# SparkFun_Qwiic_Motor_Driver.net
KiCad netlist of a schematic drawn in EAGLE
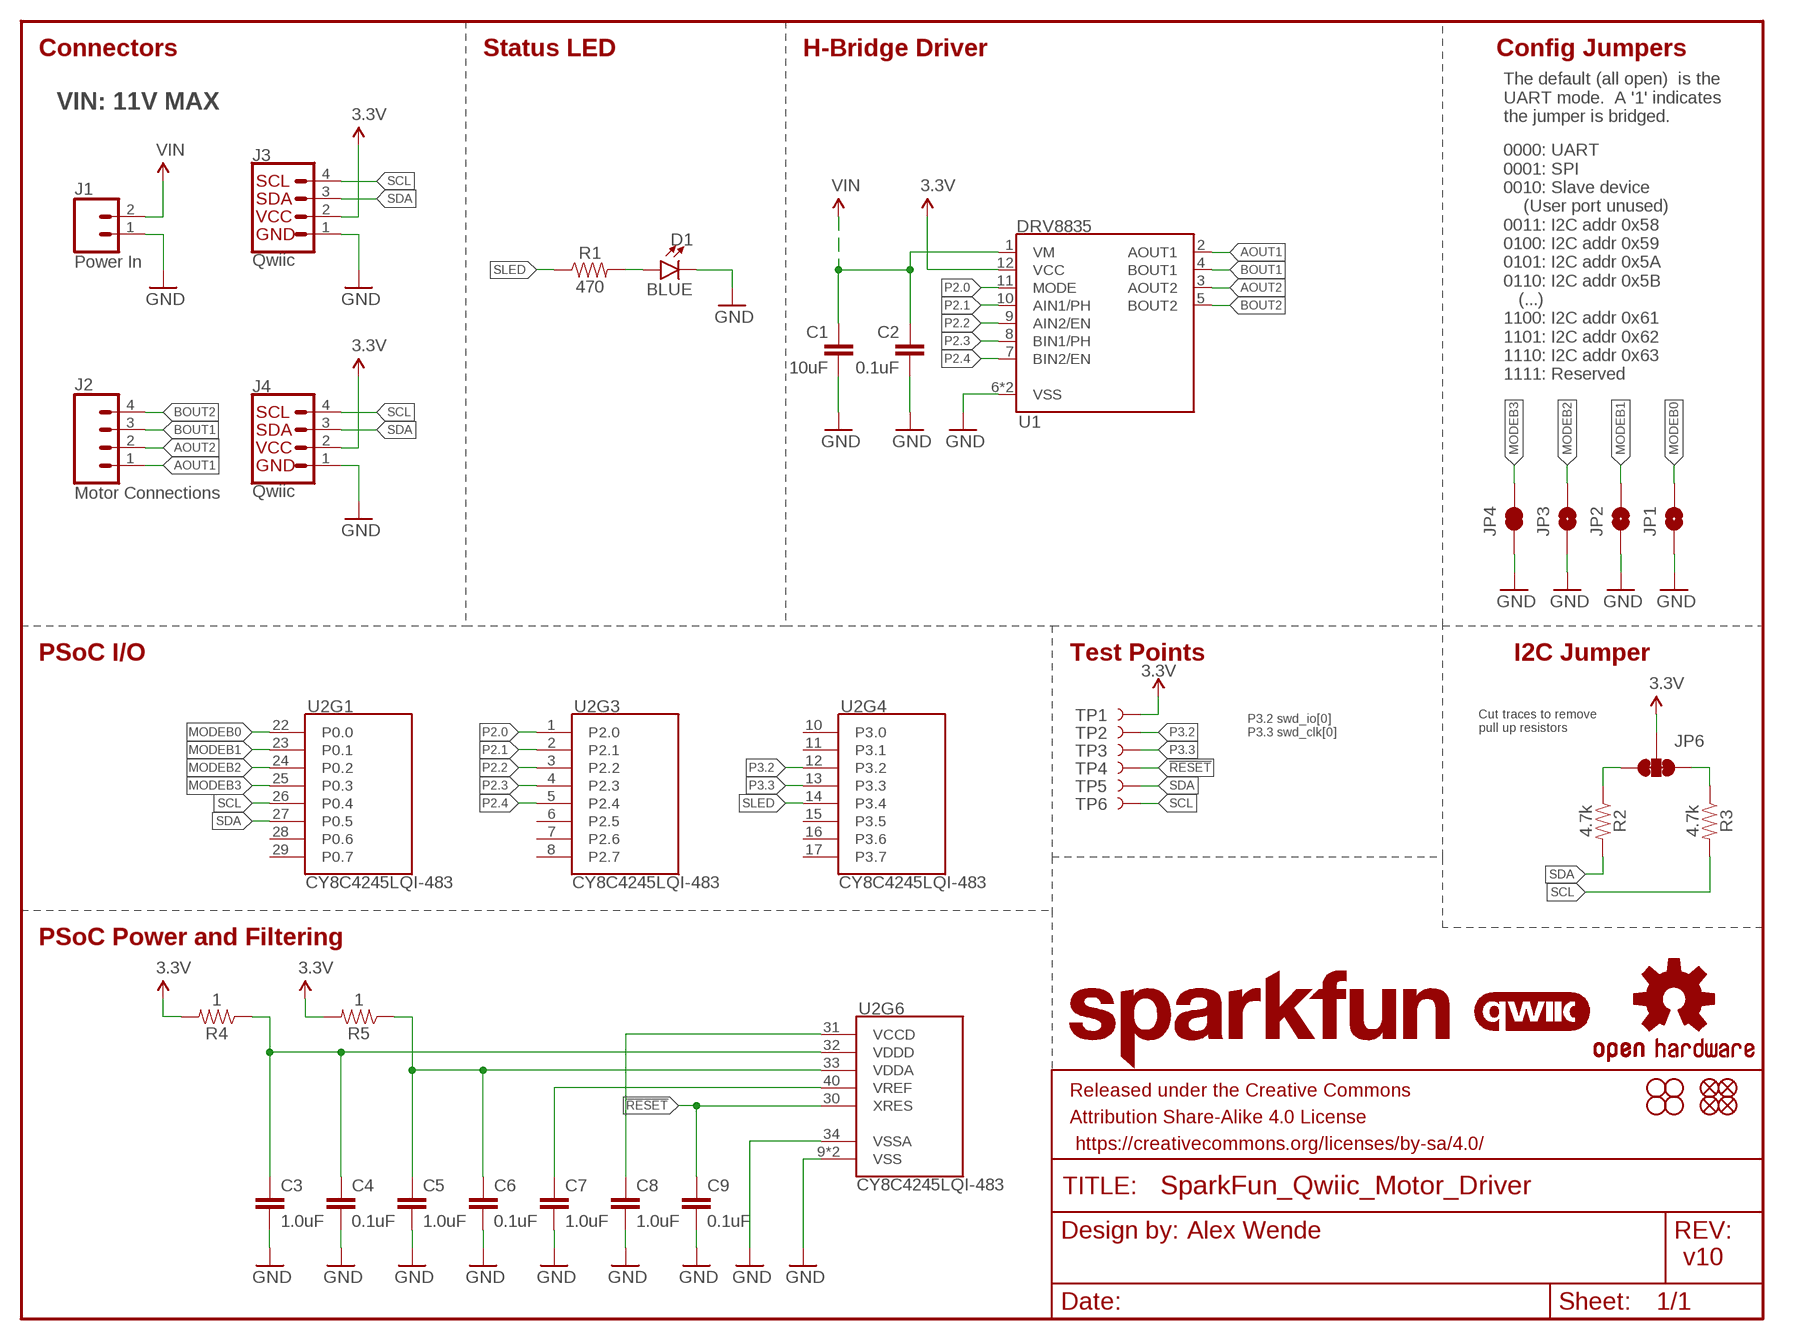
[diagram p0: schematic, sheet 1]

(export (version "E")
  (design (tool "Eeschema 10.0.6"))
  (components
    (comp (ref "C1")
      (value "10uF")
      (footprint "eagle-import:0805")
      (libsource (lib "eagle-import") (part "10UF-0805-25V-10%"))
    )
    (comp (ref "C2")
      (value "0.1uF")
      (footprint "eagle-import:0402")
      (libsource (lib "eagle-import") (part "0.1UF-0402-16V-10%"))
    )
    (comp (ref "C3")
      (value "1.0uF")
      (footprint "eagle-import:0402")
      (libsource (lib "eagle-import") (part "1.0UF-0402-16V-10%"))
    )
    (comp (ref "C4")
      (value "0.1uF")
      (footprint "eagle-import:0402")
      (libsource (lib "eagle-import") (part "0.1UF-0402-16V-10%"))
    )
    (comp (ref "C5")
      (value "1.0uF")
      (footprint "eagle-import:0402")
      (libsource (lib "eagle-import") (part "1.0UF-0402-16V-10%"))
    )
    (comp (ref "C6")
      (value "0.1uF")
      (footprint "eagle-import:0402")
      (libsource (lib "eagle-import") (part "0.1UF-0402-16V-10%"))
    )
    (comp (ref "C7")
      (value "1.0uF")
      (footprint "eagle-import:0402")
      (libsource (lib "eagle-import") (part "1.0UF-0402-16V-10%"))
    )
    (comp (ref "C8")
      (value "1.0uF")
      (footprint "eagle-import:0402")
      (libsource (lib "eagle-import") (part "1.0UF-0402-16V-10%"))
    )
    (comp (ref "C9")
      (value "0.1uF")
      (footprint "eagle-import:0402")
      (libsource (lib "eagle-import") (part "0.1UF-0402-16V-10%"))
    )
    (comp (ref "D1")
      (value "BLUE")
      (footprint "eagle-import:LED-0603")
      (libsource (lib "eagle-import") (part "LED-BLUE0603"))
    )
    (comp (ref "FD1")
      (value "FIDUCIALUFIDUCIAL")
      (footprint "eagle-import:FIDUCIAL-MICRO")
      (libsource (lib "eagle-import") (part "FIDUCIALUFIDUCIAL"))
    )
    (comp (ref "FD2")
      (value "FIDUCIALUFIDUCIAL")
      (footprint "eagle-import:FIDUCIAL-MICRO")
      (libsource (lib "eagle-import") (part "FIDUCIALUFIDUCIAL"))
    )
    (comp (ref "FD3")
      (value "FIDUCIALUFIDUCIAL")
      (footprint "eagle-import:FIDUCIAL-MICRO")
      (libsource (lib "eagle-import") (part "FIDUCIALUFIDUCIAL"))
    )
    (comp (ref "FD4")
      (value "FIDUCIALUFIDUCIAL")
      (footprint "eagle-import:FIDUCIAL-MICRO")
      (libsource (lib "eagle-import") (part "FIDUCIALUFIDUCIAL"))
    )
    (comp (ref "FRAME1")
      (value "FRAME-LETTER")
      (footprint "eagle-import:CREATIVE_COMMONS")
      (libsource (lib "eagle-import") (part "FRAME-LETTER"))
    )
    (comp (ref "H1")
      (value "STAND-OFF")
      (footprint "eagle-import:STAND-OFF")
      (libsource (lib "eagle-import") (part "STAND-OFF"))
    )
    (comp (ref "H2")
      (value "STAND-OFF")
      (footprint "eagle-import:STAND-OFF")
      (libsource (lib "eagle-import") (part "STAND-OFF"))
    )
    (comp (ref "H3")
      (value "STAND-OFF")
      (footprint "eagle-import:STAND-OFF")
      (libsource (lib "eagle-import") (part "STAND-OFF"))
    )
    (comp (ref "H4")
      (value "STAND-OFF")
      (footprint "eagle-import:STAND-OFF")
      (libsource (lib "eagle-import") (part "STAND-OFF"))
    )
    (comp (ref "J1")
      (value "Power In")
      (footprint "eagle-import:SCREWTERMINAL-3.5MM-2")
      (libsource (lib "eagle-import") (part "CONN_023.5MM"))
    )
    (comp (ref "J2")
      (value "Motor Connections")
      (footprint "eagle-import:SCREWTERMINAL-3.5MM-4")
      (libsource (lib "eagle-import") (part "CONN_04SCREW"))
    )
    (comp (ref "J3")
      (value "Qwiic")
      (footprint "eagle-import:JST04_1MM_RA")
      (libsource (lib "eagle-import") (part "QWIIC_CONNECTORJS-1MM"))
    )
    (comp (ref "J4")
      (value "Qwiic")
      (footprint "eagle-import:JST04_1MM_RA")
      (libsource (lib "eagle-import") (part "QWIIC_CONNECTORJS-1MM"))
    )
    (comp (ref "JP1")
      (value "JUMPER-PAD-2")
      (footprint "eagle-import:SMT-JUMPER_2_NO_NO-SILK")
      (libsource (lib "eagle-import") (part "JUMPER-SMT_2_NO_NO-SILK"))
    )
    (comp (ref "JP2")
      (value "JUMPER-PAD-2")
      (footprint "eagle-import:SMT-JUMPER_2_NO_NO-SILK")
      (libsource (lib "eagle-import") (part "JUMPER-SMT_2_NO_NO-SILK"))
    )
    (comp (ref "JP3")
      (value "JUMPER-PAD-2")
      (footprint "eagle-import:SMT-JUMPER_2_NO_NO-SILK")
      (libsource (lib "eagle-import") (part "JUMPER-SMT_2_NO_NO-SILK"))
    )
    (comp (ref "JP4")
      (value "JUMPER-PAD-2")
      (footprint "eagle-import:SMT-JUMPER_2_NC_TRACE_NO-SILK")
      (libsource (lib "eagle-import") (part "JUMPER-SMT_2_NC_TRACE_NO-SILK"))
    )
    (comp (ref "JP6")
      (value "JUMPER-SMT_3_2-NC_TRACE_NO-SILK")
      (footprint "eagle-import:SMT-JUMPER_3_2-NC_TRACE_NO-SILK")
      (libsource (lib "eagle-import") (part "JUMPER-SMT_3_2-NC_TRACE_NO-SILK"))
    )
    (comp (ref "LOGO2")
      (value "OSHW-LOGOMINI")
      (footprint "eagle-import:OSHW-LOGO-MINI")
      (libsource (lib "eagle-import") (part "OSHW-LOGOMINI"))
    )
    (comp (ref "LOGO3")
      (value "SFE_LOGO_NAME.1_INCH")
      (footprint "eagle-import:SFE_LOGO_NAME_.1")
      (libsource (lib "eagle-import") (part "SFE_LOGO_NAME.1_INCH"))
    )
    (comp (ref "R1")
      (value "470")
      (footprint "eagle-import:0603")
      (libsource (lib "eagle-import") (part "470OHM-0603-1/10W-1%"))
    )
    (comp (ref "R2")
      (value "4.7k")
      (footprint "eagle-import:0603")
      (libsource (lib "eagle-import") (part "4.7KOHM-0603-1/10W-1%"))
    )
    (comp (ref "R3")
      (value "4.7k")
      (footprint "eagle-import:0603")
      (libsource (lib "eagle-import") (part "4.7KOHM-0603-1/10W-1%"))
    )
    (comp (ref "R4")
      (value "1")
      (footprint "eagle-import:0603")
      (libsource (lib "eagle-import") (part "1OHM-0603-1/10W-1%"))
    )
    (comp (ref "R5")
      (value "1")
      (footprint "eagle-import:0603")
      (libsource (lib "eagle-import") (part "1OHM-0603-1/10W-1%"))
    )
    (comp (ref "TP1")
      (value "TEST-POINTTP_15TH_THRU")
      (footprint "eagle-import:TP_15TH")
      (libsource (lib "eagle-import") (part "TEST-POINTTP_15TH_THRU"))
    )
    (comp (ref "TP2")
      (value "TEST-POINTTP_15TH_THRU")
      (footprint "eagle-import:TP_15TH")
      (libsource (lib "eagle-import") (part "TEST-POINTTP_15TH_THRU"))
    )
    (comp (ref "TP3")
      (value "TEST-POINTTP_15TH_THRU")
      (footprint "eagle-import:TP_15TH")
      (libsource (lib "eagle-import") (part "TEST-POINTTP_15TH_THRU"))
    )
    (comp (ref "TP4")
      (value "TEST-POINTTP_15TH_THRU")
      (footprint "eagle-import:TP_15TH")
      (libsource (lib "eagle-import") (part "TEST-POINTTP_15TH_THRU"))
    )
    (comp (ref "TP5")
      (value "TEST-POINTTP_15TH_THRU")
      (footprint "eagle-import:TP_15TH")
      (libsource (lib "eagle-import") (part "TEST-POINTTP_15TH_THRU"))
    )
    (comp (ref "TP6")
      (value "TEST-POINTTP_15TH_THRU")
      (footprint "eagle-import:TP_15TH")
      (libsource (lib "eagle-import") (part "TEST-POINTTP_15TH_THRU"))
    )
    (comp (ref "U$1")
      (value "QWIIC_LOGO_5MM")
      (footprint "eagle-import:QWIIC_5MM")
      (libsource (lib "eagle-import") (part "QWIIC_LOGO_5MM"))
    )
    (comp (ref "U1")
      (value "DRV8835")
      (footprint "eagle-import:WSON-12")
      (fields (field (name "PROD_ID") "IC-13342"))
      (libsource (lib "eagle-import") (part "DRV883X"))
    )
    (comp (ref "U2")
      (value "CY8C4245LQI-483")
      (footprint "eagle-import:QFN-40")
      (libsource (lib "eagle-import") (part "PSOC4_4200_40QFN"))
    )
  )
  (nets
    (net (code "1") (name "/~{RESET}") (class "Default")
      (node (ref "C9") (pin "1") (pinfunction "1_1") (pintype "passive"))
      (node (ref "TP4") (pin "P$1") (pinfunction "1_P$1") (pintype "bidirectional"))
      (node (ref "U2") (pin "30") (pinfunction "XRES_30") (pintype "bidirectional"))
    )
    (net (code "2") (name "3.3V") (class "Default")
      (node (ref "J3") (pin "2") (pinfunction "2_2") (pintype "power_in"))
      (node (ref "J4") (pin "2") (pinfunction "2_2") (pintype "power_in"))
      (node (ref "JP6") (pin "2") (pinfunction "2_2") (pintype "passive"))
      (node (ref "R4") (pin "2") (pinfunction "2_2") (pintype "passive"))
      (node (ref "R5") (pin "2") (pinfunction "2_2") (pintype "passive"))
      (node (ref "TP1") (pin "P$1") (pinfunction "1_P$1") (pintype "bidirectional"))
      (node (ref "U1") (pin "12") (pinfunction "VCC_12") (pintype "bidirectional"))
    )
    (net (code "3") (name "AOUT1") (class "Default")
      (node (ref "J2") (pin "1") (pinfunction "1_1") (pintype "passive"))
      (node (ref "U1") (pin "2") (pinfunction "AOUT1_2") (pintype "bidirectional"))
    )
    (net (code "4") (name "AOUT2") (class "Default")
      (node (ref "J2") (pin "2") (pinfunction "2_2") (pintype "passive"))
      (node (ref "U1") (pin "3") (pinfunction "AOUT2_3") (pintype "bidirectional"))
    )
    (net (code "5") (name "BOUT1") (class "Default")
      (node (ref "J2") (pin "3") (pinfunction "3_3") (pintype "passive"))
      (node (ref "U1") (pin "4") (pinfunction "BOUT1_4") (pintype "bidirectional"))
    )
    (net (code "6") (name "BOUT2") (class "Default")
      (node (ref "J2") (pin "4") (pinfunction "4_4") (pintype "passive"))
      (node (ref "U1") (pin "5") (pinfunction "BOUT2_5") (pintype "bidirectional"))
    )
    (net (code "7") (name "GND") (class "Default")
      (node (ref "C1") (pin "2") (pinfunction "2_2") (pintype "passive"))
      (node (ref "C2") (pin "2") (pinfunction "2_2") (pintype "passive"))
      (node (ref "C3") (pin "2") (pinfunction "2_2") (pintype "passive"))
      (node (ref "C4") (pin "2") (pinfunction "2_2") (pintype "passive"))
      (node (ref "C5") (pin "2") (pinfunction "2_2") (pintype "passive"))
      (node (ref "C6") (pin "2") (pinfunction "2_2") (pintype "passive"))
      (node (ref "C7") (pin "2") (pinfunction "2_2") (pintype "passive"))
      (node (ref "C8") (pin "2") (pinfunction "2_2") (pintype "passive"))
      (node (ref "C9") (pin "2") (pinfunction "2_2") (pintype "passive"))
      (node (ref "D1") (pin "C") (pinfunction "C_C") (pintype "passive"))
      (node (ref "J1") (pin "1") (pinfunction "1_1") (pintype "passive"))
      (node (ref "J3") (pin "1") (pinfunction "1_1") (pintype "power_in"))
      (node (ref "J4") (pin "1") (pinfunction "1_1") (pintype "power_in"))
      (node (ref "JP1") (pin "1") (pinfunction "1_1") (pintype "passive"))
      (node (ref "JP2") (pin "1") (pinfunction "1_1") (pintype "passive"))
      (node (ref "JP3") (pin "1") (pinfunction "1_1") (pintype "passive"))
      (node (ref "JP4") (pin "1") (pinfunction "1_1") (pintype "passive"))
      (node (ref "U1") (pin "6") (pinfunction "VSS_6") (pintype "bidirectional"))
      (node (ref "U1") (pin "PAD") (pinfunction "VSS_PAD") (pintype "bidirectional"))
      (node (ref "U2") (pin "34") (pinfunction "VSSA_34") (pintype "bidirectional"))
      (node (ref "U2") (pin "9") (pinfunction "VSS_9") (pintype "bidirectional"))
      (node (ref "U2") (pin "EP") (pinfunction "VSS_EP") (pintype "bidirectional"))
    )
    (net (code "8") (name "MODEB0") (class "Default")
      (node (ref "JP1") (pin "2") (pinfunction "2_2") (pintype "passive"))
      (node (ref "U2") (pin "22") (pinfunction "P0.0_22") (pintype "bidirectional"))
    )
    (net (code "9") (name "MODEB1") (class "Default")
      (node (ref "JP2") (pin "2") (pinfunction "2_2") (pintype "passive"))
      (node (ref "U2") (pin "23") (pinfunction "P0.1_23") (pintype "bidirectional"))
    )
    (net (code "10") (name "MODEB2") (class "Default")
      (node (ref "JP3") (pin "2") (pinfunction "2_2") (pintype "passive"))
      (node (ref "U2") (pin "24") (pinfunction "P0.2_24") (pintype "bidirectional"))
    )
    (net (code "11") (name "MODEB3") (class "Default")
      (node (ref "JP4") (pin "2") (pinfunction "2_2") (pintype "passive"))
      (node (ref "U2") (pin "25") (pinfunction "P0.3_25") (pintype "bidirectional"))
    )
    (net (code "12") (name "Net-(D1-PadA)") (class "Default")
      (node (ref "D1") (pin "A") (pinfunction "A_A") (pintype "passive"))
      (node (ref "R1") (pin "2") (pinfunction "2_2") (pintype "passive"))
    )
    (net (code "13") (name "Net-(JP6-Pad1)") (class "Default")
      (node (ref "JP6") (pin "1") (pinfunction "1_1") (pintype "passive"))
      (node (ref "R3") (pin "1") (pinfunction "1_1") (pintype "passive"))
    )
    (net (code "14") (name "Net-(JP6-Pad3)") (class "Default")
      (node (ref "JP6") (pin "3") (pinfunction "3_3") (pintype "passive"))
      (node (ref "R2") (pin "1") (pinfunction "1_1") (pintype "passive"))
    )
    (net (code "15") (name "Net-(U2F-VCCD)") (class "Default")
      (node (ref "C8") (pin "1") (pinfunction "1_1") (pintype "passive"))
      (node (ref "U2") (pin "31") (pinfunction "VCCD_31") (pintype "bidirectional"))
    )
    (net (code "16") (name "Net-(U2F-VDDA)") (class "Default")
      (node (ref "C5") (pin "1") (pinfunction "1_1") (pintype "passive"))
      (node (ref "C6") (pin "1") (pinfunction "1_1") (pintype "passive"))
      (node (ref "R5") (pin "1") (pinfunction "1_1") (pintype "passive"))
      (node (ref "U2") (pin "33") (pinfunction "VDDA_33") (pintype "bidirectional"))
    )
    (net (code "17") (name "Net-(U2F-VDDD)") (class "Default")
      (node (ref "C3") (pin "1") (pinfunction "1_1") (pintype "passive"))
      (node (ref "C4") (pin "1") (pinfunction "1_1") (pintype "passive"))
      (node (ref "R4") (pin "1") (pinfunction "1_1") (pintype "passive"))
      (node (ref "U2") (pin "32") (pinfunction "VDDD_32") (pintype "bidirectional"))
    )
    (net (code "18") (name "Net-(U2F-VREF)") (class "Default")
      (node (ref "C7") (pin "1") (pinfunction "1_1") (pintype "passive"))
      (node (ref "U2") (pin "40") (pinfunction "VREF_40") (pintype "bidirectional"))
    )
    (net (code "19") (name "P2.0") (class "Default")
      (node (ref "U1") (pin "11") (pinfunction "MODE_11") (pintype "bidirectional"))
      (node (ref "U2") (pin "1") (pinfunction "P2.0_1") (pintype "bidirectional"))
    )
    (net (code "20") (name "P2.1") (class "Default")
      (node (ref "U1") (pin "10") (pinfunction "AIN1/PH_10") (pintype "bidirectional"))
      (node (ref "U2") (pin "2") (pinfunction "P2.1_2") (pintype "bidirectional"))
    )
    (net (code "21") (name "P2.2") (class "Default")
      (node (ref "U1") (pin "9") (pinfunction "AIN2/EN_9") (pintype "bidirectional"))
      (node (ref "U2") (pin "3") (pinfunction "P2.2_3") (pintype "bidirectional"))
    )
    (net (code "22") (name "P2.3") (class "Default")
      (node (ref "U1") (pin "8") (pinfunction "BIN1/PH_8") (pintype "bidirectional"))
      (node (ref "U2") (pin "4") (pinfunction "P2.3_4") (pintype "bidirectional"))
    )
    (net (code "23") (name "P2.4") (class "Default")
      (node (ref "U1") (pin "7") (pinfunction "BIN2/EN_7") (pintype "bidirectional"))
      (node (ref "U2") (pin "5") (pinfunction "P2.4_5") (pintype "bidirectional"))
    )
    (net (code "24") (name "P3.2") (class "Default")
      (node (ref "TP2") (pin "P$1") (pinfunction "1_P$1") (pintype "bidirectional"))
      (node (ref "U2") (pin "12") (pinfunction "P3.2_12") (pintype "bidirectional"))
    )
    (net (code "25") (name "P3.3") (class "Default")
      (node (ref "TP3") (pin "P$1") (pinfunction "1_P$1") (pintype "bidirectional"))
      (node (ref "U2") (pin "13") (pinfunction "P3.3_13") (pintype "bidirectional"))
    )
    (net (code "26") (name "SCL") (class "Default")
      (node (ref "J3") (pin "4") (pinfunction "4_4") (pintype "passive"))
      (node (ref "J4") (pin "4") (pinfunction "4_4") (pintype "passive"))
      (node (ref "R3") (pin "2") (pinfunction "2_2") (pintype "passive"))
      (node (ref "TP6") (pin "P$1") (pinfunction "1_P$1") (pintype "bidirectional"))
      (node (ref "U2") (pin "26") (pinfunction "P0.4_26") (pintype "bidirectional"))
    )
    (net (code "27") (name "SDA") (class "Default")
      (node (ref "J3") (pin "3") (pinfunction "3_3") (pintype "passive"))
      (node (ref "J4") (pin "3") (pinfunction "3_3") (pintype "passive"))
      (node (ref "R2") (pin "2") (pinfunction "2_2") (pintype "passive"))
      (node (ref "TP5") (pin "P$1") (pinfunction "1_P$1") (pintype "bidirectional"))
      (node (ref "U2") (pin "27") (pinfunction "P0.5_27") (pintype "bidirectional"))
    )
    (net (code "28") (name "SLED") (class "Default")
      (node (ref "R1") (pin "1") (pinfunction "1_1") (pintype "passive"))
      (node (ref "U2") (pin "14") (pinfunction "P3.4_14") (pintype "bidirectional"))
    )
    (net (code "29") (name "VIN") (class "Default")
      (node (ref "C1") (pin "1") (pinfunction "1_1") (pintype "passive"))
      (node (ref "C2") (pin "1") (pinfunction "1_1") (pintype "passive"))
      (node (ref "J1") (pin "2") (pinfunction "2_2") (pintype "passive"))
      (node (ref "U1") (pin "1") (pinfunction "VM_1") (pintype "bidirectional"))
    )
    (net (code "30") (name "unconnected-(U2A-P0.6-Pad28)") (class "Default")
      (node (ref "U2") (pin "28") (pinfunction "P0.6_28") (pintype "bidirectional"))
    )
    (net (code "31") (name "unconnected-(U2A-P0.7-Pad29)") (class "Default")
      (node (ref "U2") (pin "29") (pinfunction "P0.7_29") (pintype "bidirectional"))
    )
    (net (code "32") (name "unconnected-(U2C-P2.5-Pad6)") (class "Default")
      (node (ref "U2") (pin "6") (pinfunction "P2.5_6") (pintype "bidirectional"))
    )
    (net (code "33") (name "unconnected-(U2C-P2.6-Pad7)") (class "Default")
      (node (ref "U2") (pin "7") (pinfunction "P2.6_7") (pintype "bidirectional"))
    )
    (net (code "34") (name "unconnected-(U2C-P2.7-Pad8)") (class "Default")
      (node (ref "U2") (pin "8") (pinfunction "P2.7_8") (pintype "bidirectional"))
    )
    (net (code "35") (name "unconnected-(U2D-P3.0-Pad10)") (class "Default")
      (node (ref "U2") (pin "10") (pinfunction "P3.0_10") (pintype "bidirectional"))
    )
    (net (code "36") (name "unconnected-(U2D-P3.1-Pad11)") (class "Default")
      (node (ref "U2") (pin "11") (pinfunction "P3.1_11") (pintype "bidirectional"))
    )
    (net (code "37") (name "unconnected-(U2D-P3.5-Pad15)") (class "Default")
      (node (ref "U2") (pin "15") (pinfunction "P3.5_15") (pintype "bidirectional"))
    )
    (net (code "38") (name "unconnected-(U2D-P3.6-Pad16)") (class "Default")
      (node (ref "U2") (pin "16") (pinfunction "P3.6_16") (pintype "bidirectional"))
    )
    (net (code "39") (name "unconnected-(U2D-P3.7-Pad17)") (class "Default")
      (node (ref "U2") (pin "17") (pinfunction "P3.7_17") (pintype "bidirectional"))
    )
  )
)
